# ETH-IO_v3_1.net
KiCad netlist of a schematic drawn in EAGLE
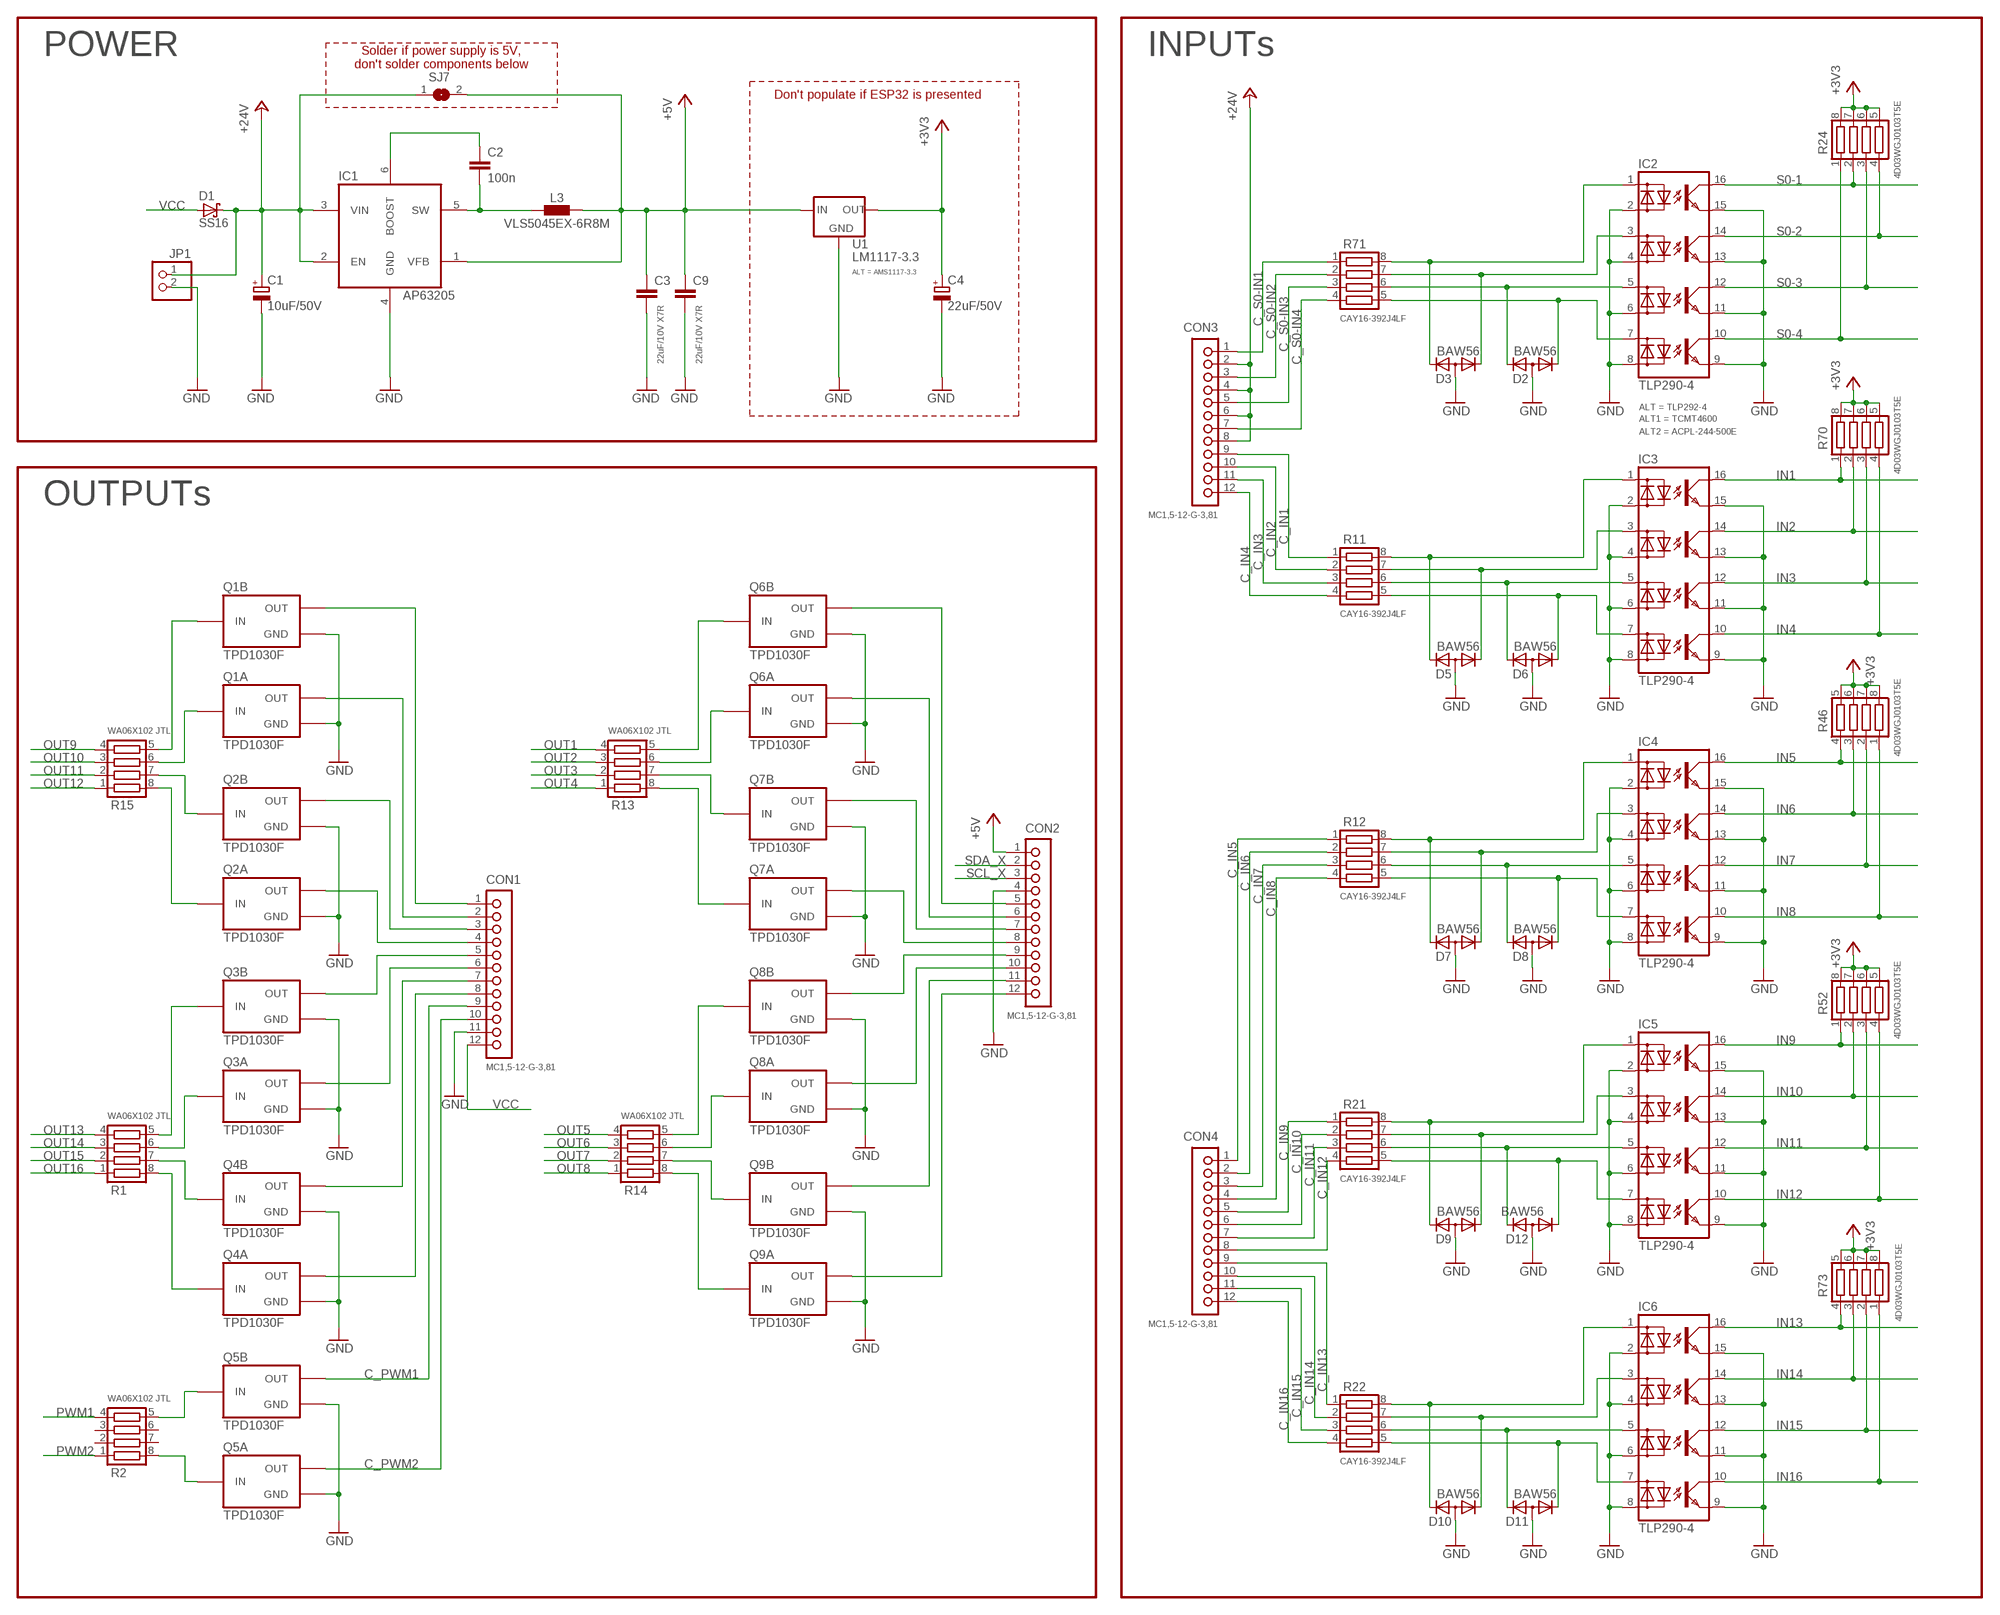
[diagram p0: schematic, sheet 1, part 1 of 2]
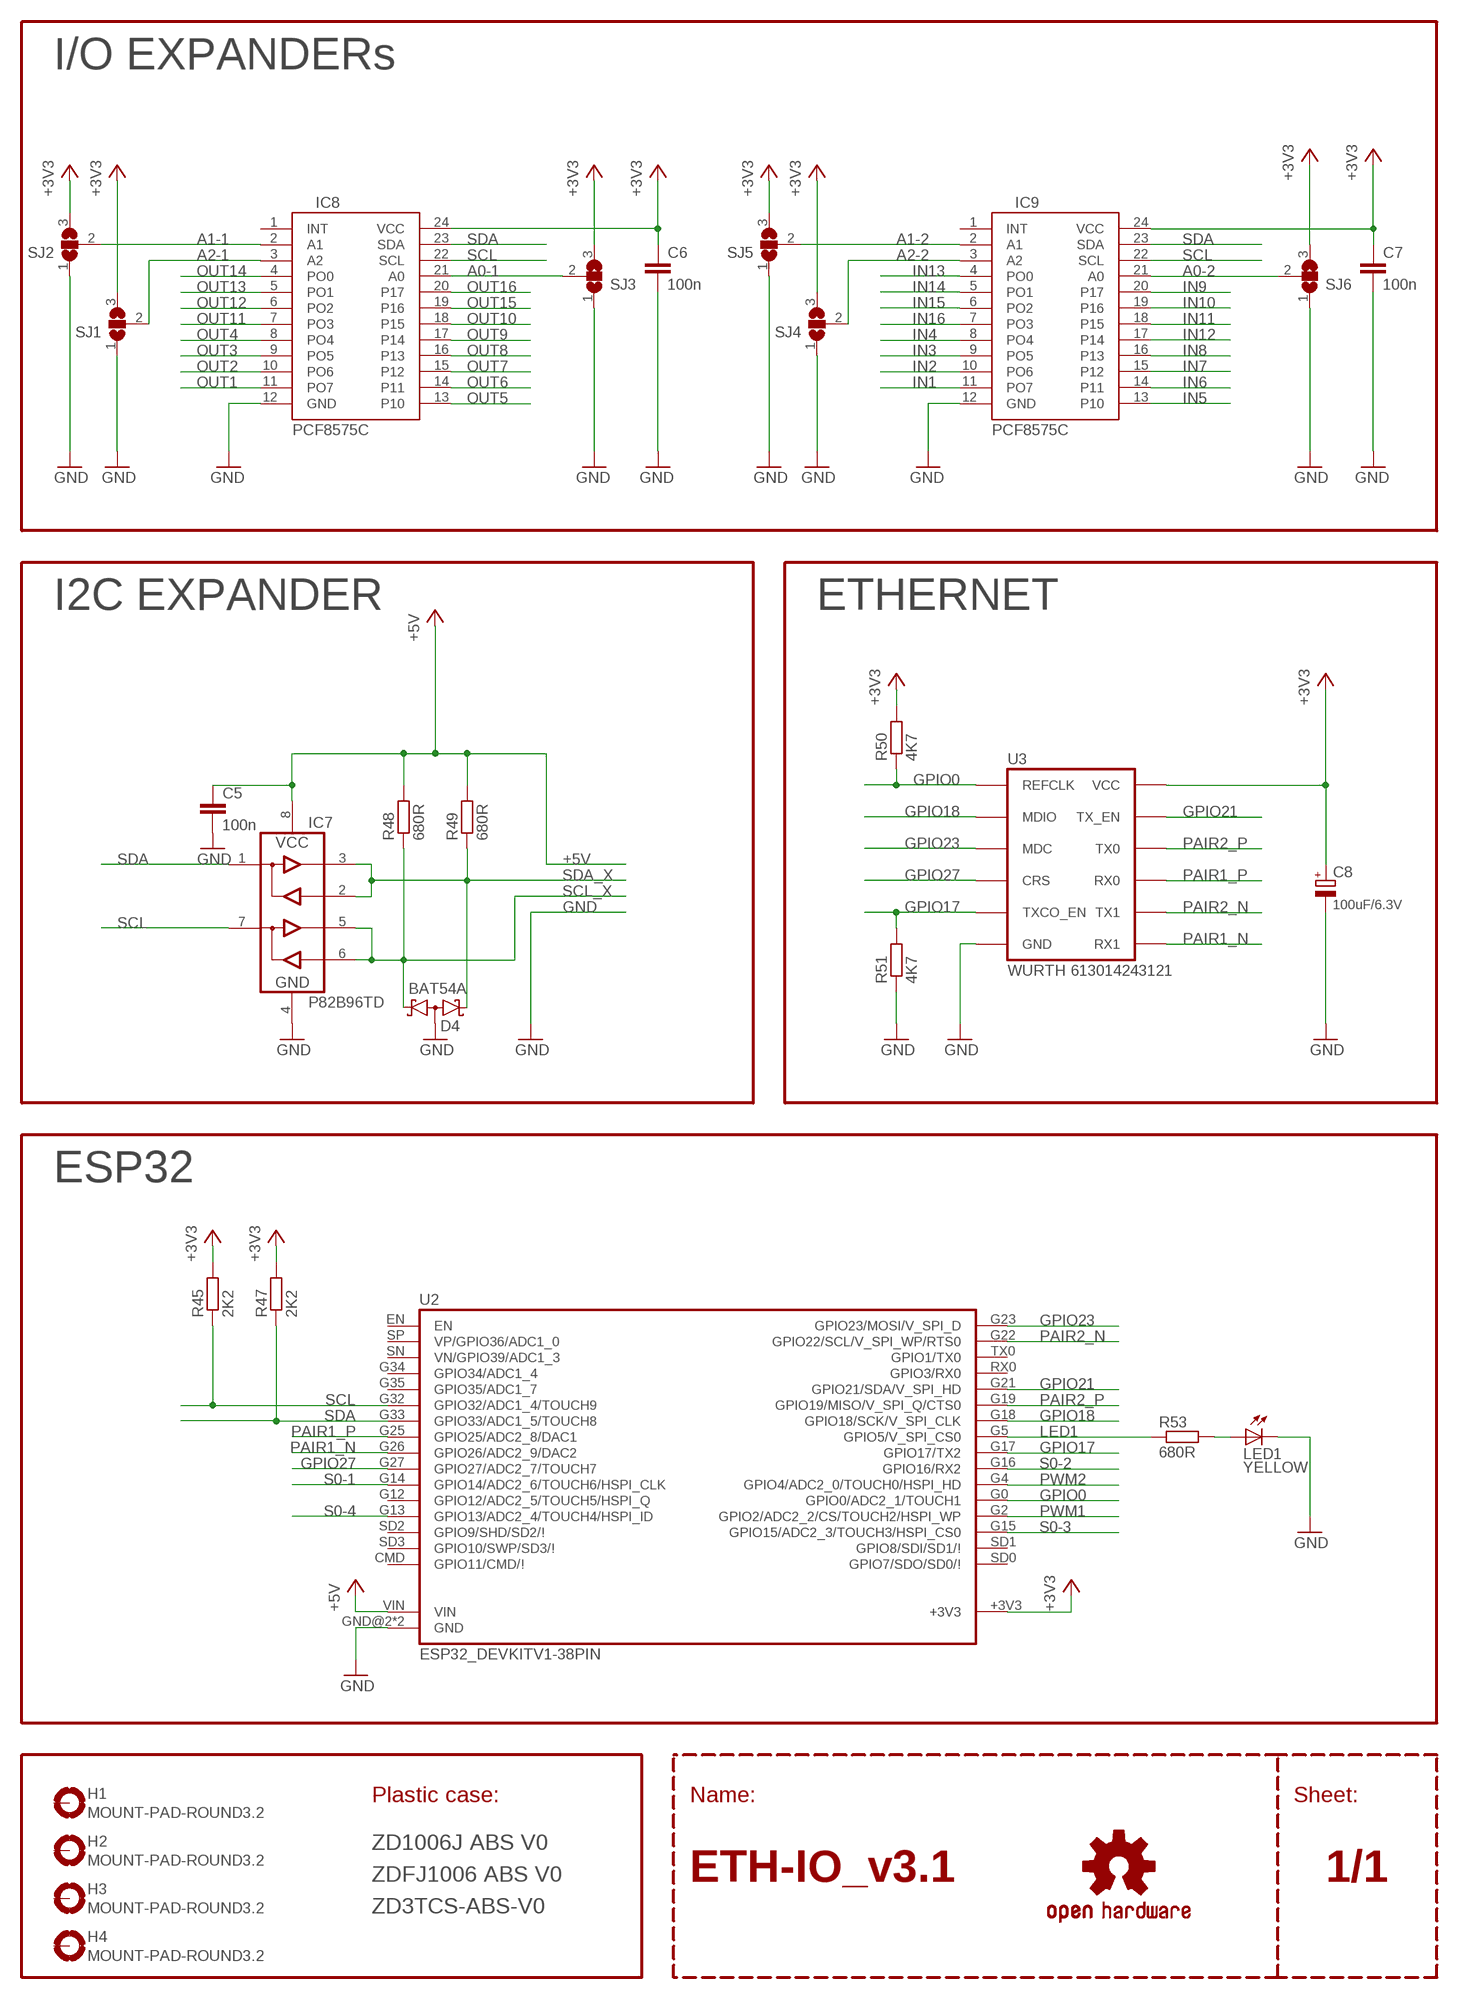
[diagram p1: schematic, sheet 1, part 2 of 2]

(export (version "E")
  (design (tool "Eeschema 10.0.6"))
  (components
    (comp (ref "C1")
      (value "10uF/50V")
      (footprint "eagle-import:PANASONIC_C")
      (libsource (lib "eagle-import") (part "CPOL-EUC"))
    )
    (comp (ref "C2")
      (value "100n")
      (footprint "eagle-import:C0805")
      (libsource (lib "eagle-import") (part "C-EUC0805"))
    )
    (comp (ref "C3")
      (value "22uF/10V X7R")
      (footprint "eagle-import:C1206")
      (libsource (lib "eagle-import") (part "C-EUC1206"))
    )
    (comp (ref "C4")
      (value "22uF/50V")
      (footprint "eagle-import:PANASONIC_C")
      (libsource (lib "eagle-import") (part "CPOL-EUC"))
    )
    (comp (ref "C5")
      (value "100n")
      (footprint "eagle-import:C0805")
      (libsource (lib "eagle-import") (part "C-EUC0805"))
    )
    (comp (ref "C6")
      (value "100n")
      (footprint "eagle-import:C0805")
      (libsource (lib "eagle-import") (part "C-EUC0805"))
    )
    (comp (ref "C7")
      (value "100n")
      (footprint "eagle-import:C0805")
      (libsource (lib "eagle-import") (part "C-EUC0805"))
    )
    (comp (ref "C8")
      (value "100uF/6.3V")
      (footprint "eagle-import:PANASONIC_C")
      (libsource (lib "eagle-import") (part "CPOL-EUC"))
    )
    (comp (ref "C9")
      (value "22uF/10V X7R")
      (footprint "eagle-import:C1206")
      (libsource (lib "eagle-import") (part "C-EUC1206"))
    )
    (comp (ref "CON1")
      (value "MC1,5-12-G-3,81")
      (footprint "eagle-import:MC1,5_12-G-3,81")
      (libsource (lib "eagle-import") (part "MC1,5-12-G-?3,81"))
    )
    (comp (ref "CON2")
      (value "MC1,5-12-G-3,81")
      (footprint "eagle-import:MC1,5_12-G-3,81")
      (libsource (lib "eagle-import") (part "MC1,5-12-G-?3,81"))
    )
    (comp (ref "CON3")
      (value "MC1,5-12-G-3,81")
      (footprint "eagle-import:MC1,5_12-G-3,81")
      (libsource (lib "eagle-import") (part "MC1,5-12-G-?3,81"))
    )
    (comp (ref "CON4")
      (value "MC1,5-12-G-3,81")
      (footprint "eagle-import:MC1,5_12-G-3,81")
      (libsource (lib "eagle-import") (part "MC1,5-12-G-?3,81"))
    )
    (comp (ref "D1")
      (value "SS16")
      (footprint "eagle-import:DO214AC")
      (libsource (lib "eagle-import") (part "SS?16"))
    )
    (comp (ref "D2")
      (value "BAW56")
      (footprint "eagle-import:SOT23")
      (libsource (lib "eagle-import") (part "BAW56"))
    )
    (comp (ref "D3")
      (value "BAW56")
      (footprint "eagle-import:SOT23")
      (libsource (lib "eagle-import") (part "BAW56"))
    )
    (comp (ref "D4")
      (value "BAT54A")
      (footprint "eagle-import:SOT23")
      (libsource (lib "eagle-import") (part "BAT54A"))
    )
    (comp (ref "D5")
      (value "BAW56")
      (footprint "eagle-import:SOT23")
      (libsource (lib "eagle-import") (part "BAW56"))
    )
    (comp (ref "D6")
      (value "BAW56")
      (footprint "eagle-import:SOT23")
      (libsource (lib "eagle-import") (part "BAW56"))
    )
    (comp (ref "D7")
      (value "BAW56")
      (footprint "eagle-import:SOT23")
      (libsource (lib "eagle-import") (part "BAW56"))
    )
    (comp (ref "D8")
      (value "BAW56")
      (footprint "eagle-import:SOT23")
      (libsource (lib "eagle-import") (part "BAW56"))
    )
    (comp (ref "D9")
      (value "BAW56")
      (footprint "eagle-import:SOT23")
      (libsource (lib "eagle-import") (part "BAW56"))
    )
    (comp (ref "D10")
      (value "BAW56")
      (footprint "eagle-import:SOT23")
      (libsource (lib "eagle-import") (part "BAW56"))
    )
    (comp (ref "D11")
      (value "BAW56")
      (footprint "eagle-import:SOT23")
      (libsource (lib "eagle-import") (part "BAW56"))
    )
    (comp (ref "D12")
      (value "BAW56")
      (footprint "eagle-import:SOT23")
      (libsource (lib "eagle-import") (part "BAW56"))
    )
    (comp (ref "H1")
      (value "MOUNT-PAD-ROUND3.2")
      (footprint "eagle-import:3,2-PAD")
      (libsource (lib "eagle-import") (part "MOUNT-PAD-ROUND3.2"))
    )
    (comp (ref "H2")
      (value "MOUNT-PAD-ROUND3.2")
      (footprint "eagle-import:3,2-PAD")
      (libsource (lib "eagle-import") (part "MOUNT-PAD-ROUND3.2"))
    )
    (comp (ref "H3")
      (value "MOUNT-PAD-ROUND3.2")
      (footprint "eagle-import:3,2-PAD")
      (libsource (lib "eagle-import") (part "MOUNT-PAD-ROUND3.2"))
    )
    (comp (ref "H4")
      (value "MOUNT-PAD-ROUND3.2")
      (footprint "eagle-import:3,2-PAD")
      (libsource (lib "eagle-import") (part "MOUNT-PAD-ROUND3.2"))
    )
    (comp (ref "IC1")
      (value "AP63205")
      (footprint "eagle-import:SOT23-6")
      (libsource (lib "eagle-import") (part "AP63205"))
    )
    (comp (ref "IC2")
      (value "TLP290-4")
      (footprint "eagle-import:SO16")
      (fields
        (field (name "ALT") "TLP292-4")
        (field (name "ALT1") "TCMT4600")
        (field (name "ALT2") "ACPL-244-500E")
      )
      (libsource (lib "eagle-import") (part "TLP290-4"))
    )
    (comp (ref "IC3")
      (value "TLP290-4")
      (footprint "eagle-import:SO16")
      (libsource (lib "eagle-import") (part "TLP290-4"))
    )
    (comp (ref "IC4")
      (value "TLP290-4")
      (footprint "eagle-import:SO16")
      (libsource (lib "eagle-import") (part "TLP290-4"))
    )
    (comp (ref "IC5")
      (value "TLP290-4")
      (footprint "eagle-import:SO16")
      (libsource (lib "eagle-import") (part "TLP290-4"))
    )
    (comp (ref "IC6")
      (value "TLP290-4")
      (footprint "eagle-import:SO16")
      (libsource (lib "eagle-import") (part "TLP290-4"))
    )
    (comp (ref "IC7")
      (value "P82B96TD")
      (footprint "eagle-import:SO08")
      (libsource (lib "eagle-import") (part "P82B96?TD"))
    )
    (comp (ref "IC8")
      (value "PCF8575C")
      (footprint "eagle-import:SO-24DW")
      (libsource (lib "eagle-import") (part "PCF8575C"))
    )
    (comp (ref "IC9")
      (value "PCF8575C")
      (footprint "eagle-import:SO-24DW")
      (libsource (lib "eagle-import") (part "PCF8575C"))
    )
    (comp (ref "JP1")
      (value "PINHD-1X2")
      (footprint "eagle-import:1X02")
      (libsource (lib "eagle-import") (part "PINHD-1X2"))
    )
    (comp (ref "L3")
      (value "VLS5045EX-6R8M")
      (footprint "eagle-import:L5040-LONGER")
      (libsource (lib "eagle-import") (part "L?5045"))
    )
    (comp (ref "LED1")
      (value "YELLOW")
      (footprint "eagle-import:LED0805")
      (libsource (lib "eagle-import") (part "LED0805"))
    )
    (comp (ref "LOGO1")
      (value "OSHW-LOGOM-COPPER")
      (footprint "eagle-import:OSHW-LOGO-M_COPPER")
      (libsource (lib "eagle-import") (part "OSHW-LOGOM-COPPER"))
    )
    (comp (ref "Q1")
      (value "TPD1030F")
      (footprint "eagle-import:SO8")
      (libsource (lib "eagle-import") (part "BTS3410G"))
    )
    (comp (ref "Q2")
      (value "TPD1030F")
      (footprint "eagle-import:SO8")
      (libsource (lib "eagle-import") (part "BTS3410G"))
    )
    (comp (ref "Q3")
      (value "TPD1030F")
      (footprint "eagle-import:SO8")
      (libsource (lib "eagle-import") (part "BTS3410G"))
    )
    (comp (ref "Q4")
      (value "TPD1030F")
      (footprint "eagle-import:SO8")
      (libsource (lib "eagle-import") (part "BTS3410G"))
    )
    (comp (ref "Q5")
      (value "TPD1030F")
      (footprint "eagle-import:SO8")
      (libsource (lib "eagle-import") (part "BTS3410G"))
    )
    (comp (ref "Q6")
      (value "TPD1030F")
      (footprint "eagle-import:SO8")
      (libsource (lib "eagle-import") (part "BTS3410G"))
    )
    (comp (ref "Q7")
      (value "TPD1030F")
      (footprint "eagle-import:SO8")
      (libsource (lib "eagle-import") (part "BTS3410G"))
    )
    (comp (ref "Q8")
      (value "TPD1030F")
      (footprint "eagle-import:SO8")
      (libsource (lib "eagle-import") (part "BTS3410G"))
    )
    (comp (ref "Q9")
      (value "TPD1030F")
      (footprint "eagle-import:SO8")
      (libsource (lib "eagle-import") (part "BTS3410G"))
    )
    (comp (ref "R1")
      (value "WA06X102 JTL")
      (footprint "eagle-import:RESCAV80P320X160X60-8N")
      (libsource (lib "eagle-import") (part "RESISTOR-ARRAY-?1206"))
    )
    (comp (ref "R2")
      (value "WA06X102 JTL")
      (footprint "eagle-import:RESCAV80P320X160X60-8N")
      (libsource (lib "eagle-import") (part "RESISTOR-ARRAY-?1206"))
    )
    (comp (ref "R11")
      (value "CAY16-392J4LF")
      (footprint "eagle-import:RESCAV80P320X160X60-8N")
      (libsource (lib "eagle-import") (part "RESISTOR-ARRAY-?1206"))
    )
    (comp (ref "R12")
      (value "CAY16-392J4LF")
      (footprint "eagle-import:RESCAV80P320X160X60-8N")
      (libsource (lib "eagle-import") (part "RESISTOR-ARRAY-?1206"))
    )
    (comp (ref "R13")
      (value "WA06X102 JTL")
      (footprint "eagle-import:RESCAV80P320X160X60-8N")
      (libsource (lib "eagle-import") (part "RESISTOR-ARRAY-?1206"))
    )
    (comp (ref "R14")
      (value "WA06X102 JTL")
      (footprint "eagle-import:RESCAV80P320X160X60-8N")
      (libsource (lib "eagle-import") (part "RESISTOR-ARRAY-?1206"))
    )
    (comp (ref "R15")
      (value "WA06X102 JTL")
      (footprint "eagle-import:RESCAV80P320X160X60-8N")
      (libsource (lib "eagle-import") (part "RESISTOR-ARRAY-?1206"))
    )
    (comp (ref "R21")
      (value "CAY16-392J4LF")
      (footprint "eagle-import:RESCAV80P320X160X60-8N")
      (libsource (lib "eagle-import") (part "RESISTOR-ARRAY-?1206"))
    )
    (comp (ref "R22")
      (value "CAY16-392J4LF")
      (footprint "eagle-import:RESCAV80P320X160X60-8N")
      (libsource (lib "eagle-import") (part "RESISTOR-ARRAY-?1206"))
    )
    (comp (ref "R24")
      (value "4D03WGJ0103T5E")
      (footprint "eagle-import:RESCAV80P320X160X60-8N")
      (libsource (lib "eagle-import") (part "RESISTOR-ARRAY-?1206"))
    )
    (comp (ref "R45")
      (value "2K2")
      (footprint "eagle-import:R0805")
      (libsource (lib "eagle-import") (part "R-EU_R0805"))
    )
    (comp (ref "R46")
      (value "4D03WGJ0103T5E")
      (footprint "eagle-import:RESCAV80P320X160X60-8N")
      (libsource (lib "eagle-import") (part "RESISTOR-ARRAY-?1206"))
    )
    (comp (ref "R47")
      (value "2K2")
      (footprint "eagle-import:R0805")
      (libsource (lib "eagle-import") (part "R-EU_R0805"))
    )
    (comp (ref "R48")
      (value "680R")
      (footprint "eagle-import:R0805")
      (libsource (lib "eagle-import") (part "R-EU_R0805"))
    )
    (comp (ref "R49")
      (value "680R")
      (footprint "eagle-import:R0805")
      (libsource (lib "eagle-import") (part "R-EU_R0805"))
    )
    (comp (ref "R50")
      (value "4K7")
      (footprint "eagle-import:R0805")
      (libsource (lib "eagle-import") (part "R-EU_R0805"))
    )
    (comp (ref "R51")
      (value "4K7")
      (footprint "eagle-import:R0805")
      (libsource (lib "eagle-import") (part "R-EU_R0805"))
    )
    (comp (ref "R52")
      (value "4D03WGJ0103T5E")
      (footprint "eagle-import:RESCAV80P320X160X60-8N")
      (libsource (lib "eagle-import") (part "RESISTOR-ARRAY-?1206"))
    )
    (comp (ref "R53")
      (value "680R")
      (footprint "eagle-import:R0805")
      (libsource (lib "eagle-import") (part "R-EU_R0805"))
    )
    (comp (ref "R70")
      (value "4D03WGJ0103T5E")
      (footprint "eagle-import:RESCAV80P320X160X60-8N")
      (libsource (lib "eagle-import") (part "RESISTOR-ARRAY-?1206"))
    )
    (comp (ref "R71")
      (value "CAY16-392J4LF")
      (footprint "eagle-import:RESCAV80P320X160X60-8N")
      (libsource (lib "eagle-import") (part "RESISTOR-ARRAY-?1206"))
    )
    (comp (ref "R73")
      (value "4D03WGJ0103T5E")
      (footprint "eagle-import:RESCAV80P320X160X60-8N")
      (libsource (lib "eagle-import") (part "RESISTOR-ARRAY-?1206"))
    )
    (comp (ref "SJ1")
      (value "SJ2W")
      (footprint "eagle-import:SJ_2")
      (libsource (lib "eagle-import") (part "SJ2W"))
    )
    (comp (ref "SJ2")
      (value "SJ2W")
      (footprint "eagle-import:SJ_2")
      (libsource (lib "eagle-import") (part "SJ2W"))
    )
    (comp (ref "SJ3")
      (value "SJ2W")
      (footprint "eagle-import:SJ_2")
      (libsource (lib "eagle-import") (part "SJ2W"))
    )
    (comp (ref "SJ4")
      (value "SJ2W")
      (footprint "eagle-import:SJ_2")
      (libsource (lib "eagle-import") (part "SJ2W"))
    )
    (comp (ref "SJ5")
      (value "SJ2W")
      (footprint "eagle-import:SJ_2")
      (libsource (lib "eagle-import") (part "SJ2W"))
    )
    (comp (ref "SJ6")
      (value "SJ2W")
      (footprint "eagle-import:SJ_2")
      (libsource (lib "eagle-import") (part "SJ2W"))
    )
    (comp (ref "SJ7") (value "SJ") (footprint "eagle-import:SJ") (libsource (lib "eagle-import") (part "SJ")))
    (comp (ref "U1")
      (value "LM1117-3.3")
      (footprint "eagle-import:SOT223")
      (fields (field (name "ALT") "AMS1117-3.3"))
      (libsource (lib "eagle-import") (part "LM1117-3.3"))
    )
    (comp (ref "U2")
      (value "ESP32_DEVKITV1-38PIN")
      (footprint "eagle-import:ESP32_DEVKITV1_38PIN")
      (libsource (lib "eagle-import") (part "ESP32_DEVKITV1-38PIN"))
    )
    (comp (ref "U3")
      (value "WURTH 613014243121")
      (footprint "eagle-import:LAN8720_ETH_BOARD")
      (libsource (lib "eagle-import") (part "LAN8720_ETH_BOARD"))
    )
  )
  (nets
    (net (code "1") (name "+3V3") (class "Default")
      (node (ref "C4") (pin "+") (pinfunction "+_+") (pintype "passive"))
      (node (ref "C6") (pin "1") (pinfunction "1_1") (pintype "passive"))
      (node (ref "C7") (pin "1") (pinfunction "1_1") (pintype "passive"))
      (node (ref "C8") (pin "+") (pinfunction "+_+") (pintype "passive"))
      (node (ref "IC8") (pin "24") (pinfunction "VCC_24") (pintype "bidirectional"))
      (node (ref "IC9") (pin "24") (pinfunction "VCC_24") (pintype "bidirectional"))
      (node (ref "R24") (pin "5") (pinfunction "4_5") (pintype "passive"))
      (node (ref "R24") (pin "6") (pinfunction "3_6") (pintype "passive"))
      (node (ref "R24") (pin "7") (pinfunction "2_7") (pintype "passive"))
      (node (ref "R24") (pin "8") (pinfunction "1_8") (pintype "passive"))
      (node (ref "R45") (pin "2") (pinfunction "2_2") (pintype "passive"))
      (node (ref "R46") (pin "5") (pinfunction "4_5") (pintype "passive"))
      (node (ref "R46") (pin "6") (pinfunction "3_6") (pintype "passive"))
      (node (ref "R46") (pin "7") (pinfunction "2_7") (pintype "passive"))
      (node (ref "R46") (pin "8") (pinfunction "1_8") (pintype "passive"))
      (node (ref "R47") (pin "2") (pinfunction "2_2") (pintype "passive"))
      (node (ref "R50") (pin "2") (pinfunction "2_2") (pintype "passive"))
      (node (ref "R52") (pin "5") (pinfunction "4_5") (pintype "passive"))
      (node (ref "R52") (pin "6") (pinfunction "3_6") (pintype "passive"))
      (node (ref "R52") (pin "7") (pinfunction "2_7") (pintype "passive"))
      (node (ref "R52") (pin "8") (pinfunction "1_8") (pintype "passive"))
      (node (ref "R70") (pin "5") (pinfunction "4_5") (pintype "passive"))
      (node (ref "R70") (pin "6") (pinfunction "3_6") (pintype "passive"))
      (node (ref "R70") (pin "7") (pinfunction "2_7") (pintype "passive"))
      (node (ref "R70") (pin "8") (pinfunction "1_8") (pintype "passive"))
      (node (ref "R73") (pin "5") (pinfunction "4_5") (pintype "passive"))
      (node (ref "R73") (pin "6") (pinfunction "3_6") (pintype "passive"))
      (node (ref "R73") (pin "7") (pinfunction "2_7") (pintype "passive"))
      (node (ref "R73") (pin "8") (pinfunction "1_8") (pintype "passive"))
      (node (ref "SJ1") (pin "3") (pinfunction "3_3") (pintype "passive"))
      (node (ref "SJ2") (pin "3") (pinfunction "3_3") (pintype "passive"))
      (node (ref "SJ3") (pin "3") (pinfunction "3_3") (pintype "passive"))
      (node (ref "SJ4") (pin "3") (pinfunction "3_3") (pintype "passive"))
      (node (ref "SJ5") (pin "3") (pinfunction "3_3") (pintype "passive"))
      (node (ref "SJ6") (pin "3") (pinfunction "3_3") (pintype "passive"))
      (node (ref "U1") (pin "2") (pinfunction "OUT_2") (pintype "output"))
      (node (ref "U1") (pin "4") (pinfunction "OUT_4") (pintype "output"))
      (node (ref "U2") (pin "+3V3") (pinfunction "+3V3_+3V3") (pintype "power_in"))
      (node (ref "U3") (pin "VCC") (pinfunction "VCC_VCC") (pintype "power_in"))
      (node (ref "U3") (pin "VCC@1") (pinfunction "VCC_VCC@1") (pintype "power_in"))
    )
    (net (code "2") (name "+5V") (class "Default")
      (node (ref "C3") (pin "1") (pinfunction "1_1") (pintype "passive"))
      (node (ref "C5") (pin "1") (pinfunction "1_1") (pintype "passive"))
      (node (ref "C9") (pin "1") (pinfunction "1_1") (pintype "passive"))
      (node (ref "CON2") (pin "1") (pinfunction "1_1") (pintype "passive"))
      (node (ref "IC1") (pin "1") (pinfunction "VFB_1") (pintype "input"))
      (node (ref "IC7") (pin "8") (pinfunction "VCC_8") (pintype "power_in"))
      (node (ref "L3") (pin "1") (pinfunction "1_1") (pintype "passive"))
      (node (ref "R48") (pin "2") (pinfunction "2_2") (pintype "passive"))
      (node (ref "R49") (pin "2") (pinfunction "2_2") (pintype "passive"))
      (node (ref "SJ7") (pin "2") (pinfunction "2_2") (pintype "passive"))
      (node (ref "U1") (pin "3") (pinfunction "IN_3") (pintype "input"))
      (node (ref "U2") (pin "VIN") (pinfunction "VIN_VIN") (pintype "power_in"))
    )
    (net (code "3") (name "+24V") (class "Default")
      (node (ref "C1") (pin "+") (pinfunction "+_+") (pintype "passive"))
      (node (ref "CON3") (pin "2") (pinfunction "2_2") (pintype "passive"))
      (node (ref "CON3") (pin "4") (pinfunction "4_4") (pintype "passive"))
      (node (ref "CON3") (pin "6") (pinfunction "6_6") (pintype "passive"))
      (node (ref "CON3") (pin "8") (pinfunction "8_8") (pintype "passive"))
      (node (ref "D1") (pin "C") (pinfunction "C_C") (pintype "passive"))
      (node (ref "IC1") (pin "2") (pinfunction "EN_2") (pintype "input"))
      (node (ref "IC1") (pin "3") (pinfunction "VIN_3") (pintype "power_in"))
      (node (ref "JP1") (pin "1") (pinfunction "1_1") (pintype "passive"))
      (node (ref "SJ7") (pin "1") (pinfunction "1_1") (pintype "passive"))
    )
    (net (code "4") (name "/A0-1") (class "Default")
      (node (ref "IC8") (pin "21") (pinfunction "A0_21") (pintype "bidirectional"))
      (node (ref "SJ3") (pin "2") (pinfunction "2_2") (pintype "passive"))
    )
    (net (code "5") (name "/A0-2") (class "Default")
      (node (ref "IC9") (pin "21") (pinfunction "A0_21") (pintype "bidirectional"))
      (node (ref "SJ6") (pin "2") (pinfunction "2_2") (pintype "passive"))
    )
    (net (code "6") (name "/A1-1") (class "Default")
      (node (ref "IC8") (pin "2") (pinfunction "A1_2") (pintype "bidirectional"))
      (node (ref "SJ2") (pin "2") (pinfunction "2_2") (pintype "passive"))
    )
    (net (code "7") (name "/A1-2") (class "Default")
      (node (ref "IC9") (pin "2") (pinfunction "A1_2") (pintype "bidirectional"))
      (node (ref "SJ5") (pin "2") (pinfunction "2_2") (pintype "passive"))
    )
    (net (code "8") (name "/A2-1") (class "Default")
      (node (ref "IC8") (pin "3") (pinfunction "A2_3") (pintype "bidirectional"))
      (node (ref "SJ1") (pin "2") (pinfunction "2_2") (pintype "passive"))
    )
    (net (code "9") (name "/A2-2") (class "Default")
      (node (ref "IC9") (pin "3") (pinfunction "A2_3") (pintype "bidirectional"))
      (node (ref "SJ4") (pin "2") (pinfunction "2_2") (pintype "passive"))
    )
    (net (code "10") (name "/C_IN1") (class "Default")
      (node (ref "CON3") (pin "9") (pinfunction "9_9") (pintype "passive"))
      (node (ref "R11") (pin "1") (pinfunction "1_1") (pintype "passive"))
    )
    (net (code "11") (name "/C_IN2") (class "Default")
      (node (ref "CON3") (pin "10") (pinfunction "10_10") (pintype "passive"))
      (node (ref "R11") (pin "2") (pinfunction "2_2") (pintype "passive"))
    )
    (net (code "12") (name "/C_IN3") (class "Default")
      (node (ref "CON3") (pin "11") (pinfunction "11_11") (pintype "passive"))
      (node (ref "R11") (pin "3") (pinfunction "3_3") (pintype "passive"))
    )
    (net (code "13") (name "/C_IN4") (class "Default")
      (node (ref "CON3") (pin "12") (pinfunction "12_12") (pintype "passive"))
      (node (ref "R11") (pin "4") (pinfunction "4_4") (pintype "passive"))
    )
    (net (code "14") (name "/C_IN5") (class "Default")
      (node (ref "CON4") (pin "1") (pinfunction "1_1") (pintype "passive"))
      (node (ref "R12") (pin "1") (pinfunction "1_1") (pintype "passive"))
    )
    (net (code "15") (name "/C_IN6") (class "Default")
      (node (ref "CON4") (pin "2") (pinfunction "2_2") (pintype "passive"))
      (node (ref "R12") (pin "2") (pinfunction "2_2") (pintype "passive"))
    )
    (net (code "16") (name "/C_IN7") (class "Default")
      (node (ref "CON4") (pin "3") (pinfunction "3_3") (pintype "passive"))
      (node (ref "R12") (pin "3") (pinfunction "3_3") (pintype "passive"))
    )
    (net (code "17") (name "/C_IN8") (class "Default")
      (node (ref "CON4") (pin "4") (pinfunction "4_4") (pintype "passive"))
      (node (ref "R12") (pin "4") (pinfunction "4_4") (pintype "passive"))
    )
    (net (code "18") (name "/C_IN9") (class "Default")
      (node (ref "CON4") (pin "5") (pinfunction "5_5") (pintype "passive"))
      (node (ref "R21") (pin "1") (pinfunction "1_1") (pintype "passive"))
    )
    (net (code "19") (name "/C_IN10") (class "Default")
      (node (ref "CON4") (pin "6") (pinfunction "6_6") (pintype "passive"))
      (node (ref "R21") (pin "2") (pinfunction "2_2") (pintype "passive"))
    )
    (net (code "20") (name "/C_IN11") (class "Default")
      (node (ref "CON4") (pin "7") (pinfunction "7_7") (pintype "passive"))
      (node (ref "R21") (pin "3") (pinfunction "3_3") (pintype "passive"))
    )
    (net (code "21") (name "/C_IN12") (class "Default")
      (node (ref "CON4") (pin "8") (pinfunction "8_8") (pintype "passive"))
      (node (ref "R21") (pin "4") (pinfunction "4_4") (pintype "passive"))
    )
    (net (code "22") (name "/C_IN13") (class "Default")
      (node (ref "CON4") (pin "9") (pinfunction "9_9") (pintype "passive"))
      (node (ref "R22") (pin "1") (pinfunction "1_1") (pintype "passive"))
    )
    (net (code "23") (name "/C_IN14") (class "Default")
      (node (ref "CON4") (pin "10") (pinfunction "10_10") (pintype "passive"))
      (node (ref "R22") (pin "2") (pinfunction "2_2") (pintype "passive"))
    )
    (net (code "24") (name "/C_IN15") (class "Default")
      (node (ref "CON4") (pin "11") (pinfunction "11_11") (pintype "passive"))
      (node (ref "R22") (pin "3") (pinfunction "3_3") (pintype "passive"))
    )
    (net (code "25") (name "/C_IN16") (class "Default")
      (node (ref "CON4") (pin "12") (pinfunction "12_12") (pintype "passive"))
      (node (ref "R22") (pin "4") (pinfunction "4_4") (pintype "passive"))
    )
    (net (code "26") (name "/C_PWM1") (class "Default")
      (node (ref "CON1") (pin "9") (pinfunction "9_9") (pintype "passive"))
      (node (ref "Q5") (pin "5") (pinfunction "OUT_5") (pintype "output"))
      (node (ref "Q5") (pin "6") (pinfunction "OUT_6") (pintype "output"))
    )
    (net (code "27") (name "/C_PWM2") (class "Default")
      (node (ref "CON1") (pin "10") (pinfunction "10_10") (pintype "passive"))
      (node (ref "Q5") (pin "7") (pinfunction "OUT_7") (pintype "output"))
      (node (ref "Q5") (pin "8") (pinfunction "OUT_8") (pintype "output"))
    )
    (net (code "28") (name "/C_S0-IN1") (class "Default")
      (node (ref "CON3") (pin "1") (pinfunction "1_1") (pintype "passive"))
      (node (ref "R71") (pin "1") (pinfunction "1_1") (pintype "passive"))
    )
    (net (code "29") (name "/C_S0-IN2") (class "Default")
      (node (ref "CON3") (pin "3") (pinfunction "3_3") (pintype "passive"))
      (node (ref "R71") (pin "2") (pinfunction "2_2") (pintype "passive"))
    )
    (net (code "30") (name "/C_S0-IN3") (class "Default")
      (node (ref "CON3") (pin "5") (pinfunction "5_5") (pintype "passive"))
      (node (ref "R71") (pin "3") (pinfunction "3_3") (pintype "passive"))
    )
    (net (code "31") (name "/C_S0-IN4") (class "Default")
      (node (ref "CON3") (pin "7") (pinfunction "7_7") (pintype "passive"))
      (node (ref "R71") (pin "4") (pinfunction "4_4") (pintype "passive"))
    )
    (net (code "32") (name "/GPIO0") (class "Default")
      (node (ref "R50") (pin "1") (pinfunction "1_1") (pintype "passive"))
      (node (ref "U2") (pin "G0") (pinfunction "GPIO0/ADC2_1/TOUCH1_G0") (pintype "bidirectional"))
      (node (ref "U3") (pin "INT") (pinfunction "REFCLK_INT") (pintype "output"))
    )
    (net (code "33") (name "/GPIO17") (class "Default")
      (node (ref "R51") (pin "2") (pinfunction "2_2") (pintype "passive"))
      (node (ref "U2") (pin "G17") (pinfunction "GPIO17/TX2_G17") (pintype "output"))
      (node (ref "U3") (pin "TXCO_EN") (pinfunction "TXCO_EN_TXCO_EN") (pintype "input"))
    )
    (net (code "34") (name "/GPIO18") (class "Default")
      (node (ref "U2") (pin "G18") (pinfunction "GPIO18/SCK/V_SPI_CLK_G18") (pintype "bidirectional"))
      (node (ref "U3") (pin "MDIO") (pinfunction "MDIO_MDIO") (pintype "bidirectional"))
    )
    (net (code "35") (name "/GPIO21") (class "Default")
      (node (ref "U2") (pin "G21") (pinfunction "GPIO21/SDA/V_SPI_HD_G21") (pintype "bidirectional"))
      (node (ref "U3") (pin "TX_EN") (pinfunction "TX_EN_TX_EN") (pintype "input"))
    )
    (net (code "36") (name "/GPIO23") (class "Default")
      (node (ref "U2") (pin "G23") (pinfunction "GPIO23/MOSI/V_SPI_D_G23") (pintype "bidirectional"))
      (node (ref "U3") (pin "MDC") (pinfunction "MDC_MDC") (pintype "bidirectional"))
    )
    (net (code "37") (name "/GPIO27") (class "Default")
      (node (ref "U2") (pin "G27") (pinfunction "GPIO27/ADC2_7/TOUCH7_G27") (pintype "bidirectional"))
      (node (ref "U3") (pin "CRS") (pinfunction "CRS_CRS") (pintype "bidirectional"))
    )
    (net (code "38") (name "/IN1") (class "Default")
      (node (ref "IC3") (pin "16") (pinfunction "COL1_16") (pintype "passive"))
      (node (ref "IC9") (pin "11") (pinfunction "PO7_11") (pintype "bidirectional"))
      (node (ref "R70") (pin "1") (pinfunction "1_1") (pintype "passive"))
    )
    (net (code "39") (name "/IN2") (class "Default")
      (node (ref "IC3") (pin "14") (pinfunction "COL2_14") (pintype "passive"))
      (node (ref "IC9") (pin "10") (pinfunction "PO6_10") (pintype "bidirectional"))
      (node (ref "R70") (pin "2") (pinfunction "2_2") (pintype "passive"))
    )
    (net (code "40") (name "/IN3") (class "Default")
      (node (ref "IC3") (pin "12") (pinfunction "COL3_12") (pintype "passive"))
      (node (ref "IC9") (pin "9") (pinfunction "PO5_9") (pintype "bidirectional"))
      (node (ref "R70") (pin "3") (pinfunction "3_3") (pintype "passive"))
    )
    (net (code "41") (name "/IN4") (class "Default")
      (node (ref "IC3") (pin "10") (pinfunction "COL4_10") (pintype "passive"))
      (node (ref "IC9") (pin "8") (pinfunction "PO4_8") (pintype "bidirectional"))
      (node (ref "R70") (pin "4") (pinfunction "4_4") (pintype "passive"))
    )
    (net (code "42") (name "/IN5") (class "Default")
      (node (ref "IC4") (pin "16") (pinfunction "COL1_16") (pintype "passive"))
      (node (ref "IC9") (pin "13") (pinfunction "P10_13") (pintype "bidirectional"))
      (node (ref "R46") (pin "4") (pinfunction "4_4") (pintype "passive"))
    )
    (net (code "43") (name "/IN6") (class "Default")
      (node (ref "IC4") (pin "14") (pinfunction "COL2_14") (pintype "passive"))
      (node (ref "IC9") (pin "14") (pinfunction "P11_14") (pintype "bidirectional"))
      (node (ref "R46") (pin "3") (pinfunction "3_3") (pintype "passive"))
    )
    (net (code "44") (name "/IN7") (class "Default")
      (node (ref "IC4") (pin "12") (pinfunction "COL3_12") (pintype "passive"))
      (node (ref "IC9") (pin "15") (pinfunction "P12_15") (pintype "bidirectional"))
      (node (ref "R46") (pin "2") (pinfunction "2_2") (pintype "passive"))
    )
    (net (code "45") (name "/IN8") (class "Default")
      (node (ref "IC4") (pin "10") (pinfunction "COL4_10") (pintype "passive"))
      (node (ref "IC9") (pin "16") (pinfunction "P13_16") (pintype "bidirectional"))
      (node (ref "R46") (pin "1") (pinfunction "1_1") (pintype "passive"))
    )
    (net (code "46") (name "/IN9") (class "Default")
      (node (ref "IC5") (pin "16") (pinfunction "COL1_16") (pintype "passive"))
      (node (ref "IC9") (pin "20") (pinfunction "P17_20") (pintype "bidirectional"))
      (node (ref "R52") (pin "1") (pinfunction "1_1") (pintype "passive"))
    )
    (net (code "47") (name "/IN10") (class "Default")
      (node (ref "IC5") (pin "14") (pinfunction "COL2_14") (pintype "passive"))
      (node (ref "IC9") (pin "19") (pinfunction "P16_19") (pintype "bidirectional"))
      (node (ref "R52") (pin "2") (pinfunction "2_2") (pintype "passive"))
    )
    (net (code "48") (name "/IN11") (class "Default")
      (node (ref "IC5") (pin "12") (pinfunction "COL3_12") (pintype "passive"))
      (node (ref "IC9") (pin "18") (pinfunction "P15_18") (pintype "bidirectional"))
      (node (ref "R52") (pin "3") (pinfunction "3_3") (pintype "passive"))
    )
    (net (code "49") (name "/IN12") (class "Default")
      (node (ref "IC5") (pin "10") (pinfunction "COL4_10") (pintype "passive"))
      (node (ref "IC9") (pin "17") (pinfunction "P14_17") (pintype "bidirectional"))
      (node (ref "R52") (pin "4") (pinfunction "4_4") (pintype "passive"))
    )
    (net (code "50") (name "/IN13") (class "Default")
      (node (ref "IC6") (pin "16") (pinfunction "COL1_16") (pintype "passive"))
      (node (ref "IC9") (pin "4") (pinfunction "PO0_4") (pintype "bidirectional"))
      (node (ref "R73") (pin "4") (pinfunction "4_4") (pintype "passive"))
    )
    (net (code "51") (name "/IN14") (class "Default")
      (node (ref "IC6") (pin "14") (pinfunction "COL2_14") (pintype "passive"))
      (node (ref "IC9") (pin "5") (pinfunction "PO1_5") (pintype "bidirectional"))
      (node (ref "R73") (pin "3") (pinfunction "3_3") (pintype "passive"))
    )
    (net (code "52") (name "/IN15") (class "Default")
      (node (ref "IC6") (pin "12") (pinfunction "COL3_12") (pintype "passive"))
      (node (ref "IC9") (pin "6") (pinfunction "PO2_6") (pintype "bidirectional"))
      (node (ref "R73") (pin "2") (pinfunction "2_2") (pintype "passive"))
    )
    (net (code "53") (name "/IN16") (class "Default")
      (node (ref "IC6") (pin "10") (pinfunction "COL4_10") (pintype "passive"))
      (node (ref "IC9") (pin "7") (pinfunction "PO3_7") (pintype "bidirectional"))
      (node (ref "R73") (pin "1") (pinfunction "1_1") (pintype "passive"))
    )
    (net (code "54") (name "/LED1") (class "Default")
      (node (ref "R53") (pin "1") (pinfunction "1_1") (pintype "passive"))
      (node (ref "U2") (pin "G5") (pinfunction "GPIO5/V_SPI_CS0_G5") (pintype "bidirectional"))
    )
    (net (code "55") (name "/OUT1") (class "Default")
      (node (ref "IC8") (pin "11") (pinfunction "PO7_11") (pintype "bidirectional"))
      (node (ref "R13") (pin "4") (pinfunction "4_4") (pintype "passive"))
    )
    (net (code "56") (name "/OUT2") (class "Default")
      (node (ref "IC8") (pin "10") (pinfunction "PO6_10") (pintype "bidirectional"))
      (node (ref "R13") (pin "3") (pinfunction "3_3") (pintype "passive"))
    )
    (net (code "57") (name "/OUT3") (class "Default")
      (node (ref "IC8") (pin "9") (pinfunction "PO5_9") (pintype "bidirectional"))
      (node (ref "R13") (pin "2") (pinfunction "2_2") (pintype "passive"))
    )
    (net (code "58") (name "/OUT4") (class "Default")
      (node (ref "IC8") (pin "8") (pinfunction "PO4_8") (pintype "bidirectional"))
      (node (ref "R13") (pin "1") (pinfunction "1_1") (pintype "passive"))
    )
    (net (code "59") (name "/OUT5") (class "Default")
      (node (ref "IC8") (pin "13") (pinfunction "P10_13") (pintype "bidirectional"))
      (node (ref "R14") (pin "4") (pinfunction "4_4") (pintype "passive"))
    )
    (net (code "60") (name "/OUT6") (class "Default")
      (node (ref "IC8") (pin "14") (pinfunction "P11_14") (pintype "bidirectional"))
      (node (ref "R14") (pin "3") (pinfunction "3_3") (pintype "passive"))
    )
    (net (code "61") (name "/OUT7") (class "Default")
      (node (ref "IC8") (pin "15") (pinfunction "P12_15") (pintype "bidirectional"))
      (node (ref "R14") (pin "2") (pinfunction "2_2") (pintype "passive"))
    )
    (net (code "62") (name "/OUT8") (class "Default")
      (node (ref "IC8") (pin "16") (pinfunction "P13_16") (pintype "bidirectional"))
      (node (ref "R14") (pin "1") (pinfunction "1_1") (pintype "passive"))
    )
    (net (code "63") (name "/OUT9") (class "Default")
      (node (ref "IC8") (pin "17") (pinfunction "P14_17") (pintype "bidirectional"))
      (node (ref "R15") (pin "4") (pinfunction "4_4") (pintype "passive"))
    )
    (net (code "64") (name "/OUT10") (class "Default")
      (node (ref "IC8") (pin "18") (pinfunction "P15_18") (pintype "bidirectional"))
      (node (ref "R15") (pin "3") (pinfunction "3_3") (pintype "passive"))
    )
    (net (code "65") (name "/OUT11") (class "Default")
      (node (ref "IC8") (pin "7") (pinfunction "PO3_7") (pintype "bidirectional"))
      (node (ref "R15") (pin "2") (pinfunction "2_2") (pintype "passive"))
    )
    (net (code "66") (name "/OUT12") (class "Default")
      (node (ref "IC8") (pin "6") (pinfunction "PO2_6") (pintype "bidirectional"))
      (node (ref "R15") (pin "1") (pinfunction "1_1") (pintype "passive"))
    )
    (net (code "67") (name "/OUT13") (class "Default")
      (node (ref "IC8") (pin "5") (pinfunction "PO1_5") (pintype "bidirectional"))
      (node (ref "R1") (pin "4") (pinfunction "4_4") (pintype "passive"))
    )
    (net (code "68") (name "/OUT14") (class "Default")
      (node (ref "IC8") (pin "4") (pinfunction "PO0_4") (pintype "bidirectional"))
      (node (ref "R1") (pin "3") (pinfunction "3_3") (pintype "passive"))
    )
    (net (code "69") (name "/OUT15") (class "Default")
      (node (ref "IC8") (pin "19") (pinfunction "P16_19") (pintype "bidirectional"))
      (node (ref "R1") (pin "2") (pinfunction "2_2") (pintype "passive"))
    )
    (net (code "70") (name "/OUT16") (class "Default")
      (node (ref "IC8") (pin "20") (pinfunction "P17_20") (pintype "bidirectional"))
      (node (ref "R1") (pin "1") (pinfunction "1_1") (pintype "passive"))
    )
    (net (code "71") (name "/PAIR1_N") (class "Default")
      (node (ref "U2") (pin "G26") (pinfunction "GPIO26/ADC2_9/DAC2_G26") (pintype "bidirectional"))
      (node (ref "U3") (pin "RX1") (pinfunction "RX1_RX1") (pintype "input"))
    )
    (net (code "72") (name "/PAIR1_P") (class "Default")
      (node (ref "U2") (pin "G25") (pinfunction "GPIO25/ADC2_8/DAC1_G25") (pintype "bidirectional"))
      (node (ref "U3") (pin "RX0") (pinfunction "RX0_RX0") (pintype "input"))
    )
    (net (code "73") (name "/PAIR2_N") (class "Default")
      (node (ref "U2") (pin "G22") (pinfunction "GPIO22/SCL/V_SPI_WP/RTS0_G22") (pintype "bidirectional"))
      (node (ref "U3") (pin "TX1") (pinfunction "TX1_TX1") (pintype "output"))
    )
    (net (code "74") (name "/PAIR2_P") (class "Default")
      (node (ref "U2") (pin "G19") (pinfunction "GPIO19/MISO/V_SPI_Q/CTS0_G19") (pintype "bidirectional"))
      (node (ref "U3") (pin "TX0") (pinfunction "TX0_TX0") (pintype "output"))
    )
    (net (code "75") (name "/PWM1") (class "Default")
      (node (ref "R2") (pin "4") (pinfunction "4_4") (pintype "passive"))
      (node (ref "U2") (pin "G2") (pinfunction "GPIO2/ADC2_2/CS/TOUCH2/HSPI_WP_G2") (pintype "bidirectional"))
    )
    (net (code "76") (name "/PWM2") (class "Default")
      (node (ref "R2") (pin "1") (pinfunction "1_1") (pintype "passive"))
      (node (ref "U2") (pin "G4") (pinfunction "GPIO4/ADC2_0/TOUCH0/HSPI_HD_G4") (pintype "bidirectional"))
    )
    (net (code "77") (name "/S0-1") (class "Default")
      (node (ref "IC2") (pin "16") (pinfunction "COL1_16") (pintype "passive"))
      (node (ref "R24") (pin "2") (pinfunction "2_2") (pintype "passive"))
      (node (ref "U2") (pin "G14") (pinfunction "GPIO14/ADC2_6/TOUCH6/HSPI_CLK_G14") (pintype "bidirectional"))
    )
    (net (code "78") (name "/S0-2") (class "Default")
      (node (ref "IC2") (pin "14") (pinfunction "COL2_14") (pintype "passive"))
      (node (ref "R24") (pin "4") (pinfunction "4_4") (pintype "passive"))
      (node (ref "U2") (pin "G16") (pinfunction "GPIO16/RX2_G16") (pintype "input"))
    )
    (net (code "79") (name "/S0-3") (class "Default")
      (node (ref "IC2") (pin "12") (pinfunction "COL3_12") (pintype "passive"))
      (node (ref "R24") (pin "3") (pinfunction "3_3") (pintype "passive"))
      (node (ref "U2") (pin "G15") (pinfunction "GPIO15/ADC2_3/TOUCH3/HSPI_CS0_G15") (pintype "bidirectional"))
    )
    (net (code "80") (name "/S0-4") (class "Default")
      (node (ref "IC2") (pin "10") (pinfunction "COL4_10") (pintype "passive"))
      (node (ref "R24") (pin "1") (pinfunction "1_1") (pintype "passive"))
      (node (ref "U2") (pin "G13") (pinfunction "GPIO13/ADC2_4/TOUCH4/HSPI_ID_G13") (pintype "bidirectional"))
    )
    (net (code "81") (name "/SCL") (class "Default")
      (node (ref "IC7") (pin "7") (pinfunction "SY_7") (pintype "input"))
      (node (ref "IC8") (pin "22") (pinfunction "SCL_22") (pintype "bidirectional"))
      (node (ref "IC9") (pin "22") (pinfunction "SCL_22") (pintype "bidirectional"))
      (node (ref "R45") (pin "1") (pinfunction "1_1") (pintype "passive"))
      (node (ref "U2") (pin "G32") (pinfunction "GPIO32/ADC1_4/TOUCH9_G32") (pintype "bidirectional"))
    )
    (net (code "82") (name "/SCL_X") (class "Default")
      (node (ref "CON2") (pin "3") (pinfunction "3_3") (pintype "passive"))
      (node (ref "D4") (pin "1") (pinfunction "K1_1") (pintype "passive"))
      (node (ref "IC7") (pin "5") (pinfunction "TY_5") (pintype "open_collector"))
      (node (ref "IC7") (pin "6") (pinfunction "RY_6") (pintype "open_collector"))
      (node (ref "R48") (pin "1") (pinfunction "1_1") (pintype "passive"))
    )
    (net (code "83") (name "/SDA") (class "Default")
      (node (ref "IC7") (pin "1") (pinfunction "SX_1") (pintype "input"))
      (node (ref "IC8") (pin "23") (pinfunction "SDA_23") (pintype "bidirectional"))
      (node (ref "IC9") (pin "23") (pinfunction "SDA_23") (pintype "bidirectional"))
      (node (ref "R47") (pin "1") (pinfunction "1_1") (pintype "passive"))
      (node (ref "U2") (pin "G33") (pinfunction "GPIO33/ADC1_5/TOUCH8_G33") (pintype "bidirectional"))
    )
    (net (code "84") (name "/SDA_X") (class "Default")
      (node (ref "CON2") (pin "2") (pinfunction "2_2") (pintype "passive"))
      (node (ref "D4") (pin "2") (pinfunction "K2_2") (pintype "passive"))
      (node (ref "IC7") (pin "2") (pinfunction "RX_2") (pintype "open_collector"))
      (node (ref "IC7") (pin "3") (pinfunction "TX_3") (pintype "open_collector"))
      (node (ref "R49") (pin "1") (pinfunction "1_1") (pintype "passive"))
    )
    (net (code "85") (name "/VCC") (class "Default")
      (node (ref "CON1") (pin "12") (pinfunction "12_12") (pintype "passive"))
      (node (ref "D1") (pin "A") (pinfunction "A_A") (pintype "passive"))
    )
    (net (code "86") (name "GND") (class "Default")
      (node (ref "C1") (pin "-") (pinfunction "-_-") (pintype "passive"))
      (node (ref "C3") (pin "2") (pinfunction "2_2") (pintype "passive"))
      (node (ref "C4") (pin "-") (pinfunction "-_-") (pintype "passive"))
      (node (ref "C5") (pin "2") (pinfunction "2_2") (pintype "passive"))
      (node (ref "C6") (pin "2") (pinfunction "2_2") (pintype "passive"))
      (node (ref "C7") (pin "2") (pinfunction "2_2") (pintype "passive"))
      (node (ref "C8") (pin "-") (pinfunction "-_-") (pintype "passive"))
      (node (ref "C9") (pin "2") (pinfunction "2_2") (pintype "passive"))
      (node (ref "CON1") (pin "11") (pinfunction "11_11") (pintype "passive"))
      (node (ref "CON2") (pin "4") (pinfunction "4_4") (pintype "passive"))
      (node (ref "D10") (pin "3") (pinfunction "A_3") (pintype "passive"))
      (node (ref "D11") (pin "3") (pinfunction "A_3") (pintype "passive"))
      (node (ref "D12") (pin "3") (pinfunction "A_3") (pintype "passive"))
      (node (ref "D2") (pin "3") (pinfunction "A_3") (pintype "passive"))
      (node (ref "D3") (pin "3") (pinfunction "A_3") (pintype "passive"))
      (node (ref "D4") (pin "3") (pinfunction "AA_3") (pintype "passive"))
      (node (ref "D5") (pin "3") (pinfunction "A_3") (pintype "passive"))
      (node (ref "D6") (pin "3") (pinfunction "A_3") (pintype "passive"))
      (node (ref "D7") (pin "3") (pinfunction "A_3") (pintype "passive"))
      (node (ref "D8") (pin "3") (pinfunction "A_3") (pintype "passive"))
      (node (ref "D9") (pin "3") (pinfunction "A_3") (pintype "passive"))
      (node (ref "IC1") (pin "4") (pinfunction "GND_4") (pintype "power_in"))
      (node (ref "IC2") (pin "11") (pinfunction "EMIT3_11") (pintype "passive"))
      (node (ref "IC2") (pin "13") (pinfunction "EMIT2_13") (pintype "passive"))
      (node (ref "IC2") (pin "15") (pinfunction "EMIT1_15") (pintype "passive"))
      (node (ref "IC2") (pin "2") (pinfunction "C1_2") (pintype "passive"))
      (node (ref "IC2") (pin "4") (pinfunction "C2_4") (pintype "passive"))
      (node (ref "IC2") (pin "6") (pinfunction "C3_6") (pintype "passive"))
      (node (ref "IC2") (pin "8") (pinfunction "C4_8") (pintype "passive"))
      (node (ref "IC2") (pin "9") (pinfunction "EMIT4_9") (pintype "passive"))
      (node (ref "IC3") (pin "11") (pinfunction "EMIT3_11") (pintype "passive"))
      (node (ref "IC3") (pin "13") (pinfunction "EMIT2_13") (pintype "passive"))
      (node (ref "IC3") (pin "15") (pinfunction "EMIT1_15") (pintype "passive"))
      (node (ref "IC3") (pin "2") (pinfunction "C1_2") (pintype "passive"))
      (node (ref "IC3") (pin "4") (pinfunction "C2_4") (pintype "passive"))
      (node (ref "IC3") (pin "6") (pinfunction "C3_6") (pintype "passive"))
      (node (ref "IC3") (pin "8") (pinfunction "C4_8") (pintype "passive"))
      (node (ref "IC3") (pin "9") (pinfunction "EMIT4_9") (pintype "passive"))
      (node (ref "IC4") (pin "11") (pinfunction "EMIT3_11") (pintype "passive"))
      (node (ref "IC4") (pin "13") (pinfunction "EMIT2_13") (pintype "passive"))
      (node (ref "IC4") (pin "15") (pinfunction "EMIT1_15") (pintype "passive"))
      (node (ref "IC4") (pin "2") (pinfunction "C1_2") (pintype "passive"))
      (node (ref "IC4") (pin "4") (pinfunction "C2_4") (pintype "passive"))
      (node (ref "IC4") (pin "6") (pinfunction "C3_6") (pintype "passive"))
      (node (ref "IC4") (pin "8") (pinfunction "C4_8") (pintype "passive"))
      (node (ref "IC4") (pin "9") (pinfunction "EMIT4_9") (pintype "passive"))
      (node (ref "IC5") (pin "11") (pinfunction "EMIT3_11") (pintype "passive"))
      (node (ref "IC5") (pin "13") (pinfunction "EMIT2_13") (pintype "passive"))
      (node (ref "IC5") (pin "15") (pinfunction "EMIT1_15") (pintype "passive"))
      (node (ref "IC5") (pin "2") (pinfunction "C1_2") (pintype "passive"))
      (node (ref "IC5") (pin "4") (pinfunction "C2_4") (pintype "passive"))
      (node (ref "IC5") (pin "6") (pinfunction "C3_6") (pintype "passive"))
      (node (ref "IC5") (pin "8") (pinfunction "C4_8") (pintype "passive"))
      (node (ref "IC5") (pin "9") (pinfunction "EMIT4_9") (pintype "passive"))
      (node (ref "IC6") (pin "11") (pinfunction "EMIT3_11") (pintype "passive"))
      (node (ref "IC6") (pin "13") (pinfunction "EMIT2_13") (pintype "passive"))
      (node (ref "IC6") (pin "15") (pinfunction "EMIT1_15") (pintype "passive"))
      (node (ref "IC6") (pin "2") (pinfunction "C1_2") (pintype "passive"))
      (node (ref "IC6") (pin "4") (pinfunction "C2_4") (pintype "passive"))
      (node (ref "IC6") (pin "6") (pinfunction "C3_6") (pintype "passive"))
      (node (ref "IC6") (pin "8") (pinfunction "C4_8") (pintype "passive"))
      (node (ref "IC6") (pin "9") (pinfunction "EMIT4_9") (pintype "passive"))
      (node (ref "IC7") (pin "4") (pinfunction "GND_4") (pintype "power_in"))
      (node (ref "IC8") (pin "12") (pinfunction "GND_12") (pintype "bidirectional"))
      (node (ref "IC9") (pin "12") (pinfunction "GND_12") (pintype "bidirectional"))
      (node (ref "JP1") (pin "2") (pinfunction "2_2") (pintype "passive"))
      (node (ref "LED1") (pin "C") (pinfunction "C_C") (pintype "passive"))
      (node (ref "Q1") (pin "1") (pinfunction "GND_1") (pintype "power_in"))
      (node (ref "Q1") (pin "3") (pinfunction "GND_3") (pintype "power_in"))
      (node (ref "Q2") (pin "1") (pinfunction "GND_1") (pintype "power_in"))
      (node (ref "Q2") (pin "3") (pinfunction "GND_3") (pintype "power_in"))
      (node (ref "Q3") (pin "1") (pinfunction "GND_1") (pintype "power_in"))
      (node (ref "Q3") (pin "3") (pinfunction "GND_3") (pintype "power_in"))
      (node (ref "Q4") (pin "1") (pinfunction "GND_1") (pintype "power_in"))
      (node (ref "Q4") (pin "3") (pinfunction "GND_3") (pintype "power_in"))
      (node (ref "Q5") (pin "1") (pinfunction "GND_1") (pintype "power_in"))
      (node (ref "Q5") (pin "3") (pinfunction "GND_3") (pintype "power_in"))
      (node (ref "Q6") (pin "1") (pinfunction "GND_1") (pintype "power_in"))
      (node (ref "Q6") (pin "3") (pinfunction "GND_3") (pintype "power_in"))
      (node (ref "Q7") (pin "1") (pinfunction "GND_1") (pintype "power_in"))
      (node (ref "Q7") (pin "3") (pinfunction "GND_3") (pintype "power_in"))
      (node (ref "Q8") (pin "1") (pinfunction "GND_1") (pintype "power_in"))
      (node (ref "Q8") (pin "3") (pinfunction "GND_3") (pintype "power_in"))
      (node (ref "Q9") (pin "1") (pinfunction "GND_1") (pintype "power_in"))
      (node (ref "Q9") (pin "3") (pinfunction "GND_3") (pintype "power_in"))
      (node (ref "R51") (pin "1") (pinfunction "1_1") (pintype "passive"))
      (node (ref "SJ1") (pin "1") (pinfunction "1_1") (pintype "passive"))
      (node (ref "SJ2") (pin "1") (pinfunction "1_1") (pintype "passive"))
      (node (ref "SJ3") (pin "1") (pinfunction "1_1") (pintype "passive"))
      (node (ref "SJ4") (pin "1") (pinfunction "1_1") (pintype "passive"))
      (node (ref "SJ5") (pin "1") (pinfunction "1_1") (pintype "passive"))
      (node (ref "SJ6") (pin "1") (pinfunction "1_1") (pintype "passive"))
      (node (ref "U1") (pin "1") (pinfunction "GND_1") (pintype "input"))
      (node (ref "U2") (pin "GND@2") (pinfunction "GND_GND@2") (pintype "power_in"))
      (node (ref "U2") (pin "GND@3") (pinfunction "GND_GND@3") (pintype "power_in"))
      (node (ref "U3") (pin "GND") (pinfunction "GND_GND") (pintype "power_in"))
      (node (ref "U3") (pin "GND@1") (pinfunction "GND_GND@1") (pintype "power_in"))
    )
    (net (code "87") (name "Net-(CON1-Pad1)") (class "Default")
      (node (ref "CON1") (pin "1") (pinfunction "1_1") (pintype "passive"))
      (node (ref "Q1") (pin "5") (pinfunction "OUT_5") (pintype "output"))
      (node (ref "Q1") (pin "6") (pinfunction "OUT_6") (pintype "output"))
    )
    (net (code "88") (name "Net-(CON1-Pad2)") (class "Default")
      (node (ref "CON1") (pin "2") (pinfunction "2_2") (pintype "passive"))
      (node (ref "Q1") (pin "7") (pinfunction "OUT_7") (pintype "output"))
      (node (ref "Q1") (pin "8") (pinfunction "OUT_8") (pintype "output"))
    )
    (net (code "89") (name "Net-(CON1-Pad3)") (class "Default")
      (node (ref "CON1") (pin "3") (pinfunction "3_3") (pintype "passive"))
      (node (ref "Q2") (pin "5") (pinfunction "OUT_5") (pintype "output"))
      (node (ref "Q2") (pin "6") (pinfunction "OUT_6") (pintype "output"))
    )
    (net (code "90") (name "Net-(CON1-Pad4)") (class "Default")
      (node (ref "CON1") (pin "4") (pinfunction "4_4") (pintype "passive"))
      (node (ref "Q2") (pin "7") (pinfunction "OUT_7") (pintype "output"))
      (node (ref "Q2") (pin "8") (pinfunction "OUT_8") (pintype "output"))
    )
    (net (code "91") (name "Net-(CON1-Pad5)") (class "Default")
      (node (ref "CON1") (pin "5") (pinfunction "5_5") (pintype "passive"))
      (node (ref "Q3") (pin "5") (pinfunction "OUT_5") (pintype "output"))
      (node (ref "Q3") (pin "6") (pinfunction "OUT_6") (pintype "output"))
    )
    (net (code "92") (name "Net-(CON1-Pad6)") (class "Default")
      (node (ref "CON1") (pin "6") (pinfunction "6_6") (pintype "passive"))
      (node (ref "Q3") (pin "7") (pinfunction "OUT_7") (pintype "output"))
      (node (ref "Q3") (pin "8") (pinfunction "OUT_8") (pintype "output"))
    )
    (net (code "93") (name "Net-(CON1-Pad7)") (class "Default")
      (node (ref "CON1") (pin "7") (pinfunction "7_7") (pintype "passive"))
      (node (ref "Q4") (pin "5") (pinfunction "OUT_5") (pintype "output"))
      (node (ref "Q4") (pin "6") (pinfunction "OUT_6") (pintype "output"))
    )
    (net (code "94") (name "Net-(CON1-Pad8)") (class "Default")
      (node (ref "CON1") (pin "8") (pinfunction "8_8") (pintype "passive"))
      (node (ref "Q4") (pin "7") (pinfunction "OUT_7") (pintype "output"))
      (node (ref "Q4") (pin "8") (pinfunction "OUT_8") (pintype "output"))
    )
    (net (code "95") (name "Net-(CON2-Pad5)") (class "Default")
      (node (ref "CON2") (pin "5") (pinfunction "5_5") (pintype "passive"))
      (node (ref "Q6") (pin "5") (pinfunction "OUT_5") (pintype "output"))
      (node (ref "Q6") (pin "6") (pinfunction "OUT_6") (pintype "output"))
    )
    (net (code "96") (name "Net-(CON2-Pad6)") (class "Default")
      (node (ref "CON2") (pin "6") (pinfunction "6_6") (pintype "passive"))
      (node (ref "Q6") (pin "7") (pinfunction "OUT_7") (pintype "output"))
      (node (ref "Q6") (pin "8") (pinfunction "OUT_8") (pintype "output"))
    )
    (net (code "97") (name "Net-(CON2-Pad7)") (class "Default")
      (node (ref "CON2") (pin "7") (pinfunction "7_7") (pintype "passive"))
      (node (ref "Q7") (pin "5") (pinfunction "OUT_5") (pintype "output"))
      (node (ref "Q7") (pin "6") (pinfunction "OUT_6") (pintype "output"))
    )
    (net (code "98") (name "Net-(CON2-Pad8)") (class "Default")
      (node (ref "CON2") (pin "8") (pinfunction "8_8") (pintype "passive"))
      (node (ref "Q7") (pin "7") (pinfunction "OUT_7") (pintype "output"))
      (node (ref "Q7") (pin "8") (pinfunction "OUT_8") (pintype "output"))
    )
    (net (code "99") (name "Net-(CON2-Pad9)") (class "Default")
      (node (ref "CON2") (pin "9") (pinfunction "9_9") (pintype "passive"))
      (node (ref "Q8") (pin "5") (pinfunction "OUT_5") (pintype "output"))
      (node (ref "Q8") (pin "6") (pinfunction "OUT_6") (pintype "output"))
    )
    (net (code "100") (name "Net-(CON2-Pad10)") (class "Default")
      (node (ref "CON2") (pin "10") (pinfunction "10_10") (pintype "passive"))
      (node (ref "Q8") (pin "7") (pinfunction "OUT_7") (pintype "output"))
      (node (ref "Q8") (pin "8") (pinfunction "OUT_8") (pintype "output"))
    )
    (net (code "101") (name "Net-(CON2-Pad11)") (class "Default")
      (node (ref "CON2") (pin "11") (pinfunction "11_11") (pintype "passive"))
      (node (ref "Q9") (pin "5") (pinfunction "OUT_5") (pintype "output"))
      (node (ref "Q9") (pin "6") (pinfunction "OUT_6") (pintype "output"))
    )
    (net (code "102") (name "Net-(CON2-Pad12)") (class "Default")
      (node (ref "CON2") (pin "12") (pinfunction "12_12") (pintype "passive"))
      (node (ref "Q9") (pin "7") (pinfunction "OUT_7") (pintype "output"))
      (node (ref "Q9") (pin "8") (pinfunction "OUT_8") (pintype "output"))
    )
    (net (code "103") (name "Net-(D2-K1)") (class "Default")
      (node (ref "D2") (pin "1") (pinfunction "K1_1") (pintype "passive"))
      (node (ref "IC2") (pin "7") (pinfunction "A4_7") (pintype "passive"))
      (node (ref "R71") (pin "5") (pinfunction "4_5") (pintype "passive"))
    )
    (net (code "104") (name "Net-(D2-K2)") (class "Default")
      (node (ref "D2") (pin "2") (pinfunction "K2_2") (pintype "passive"))
      (node (ref "IC2") (pin "5") (pinfunction "A3_5") (pintype "passive"))
      (node (ref "R71") (pin "6") (pinfunction "3_6") (pintype "passive"))
    )
    (net (code "105") (name "Net-(D3-K1)") (class "Default")
      (node (ref "D3") (pin "1") (pinfunction "K1_1") (pintype "passive"))
      (node (ref "IC2") (pin "3") (pinfunction "A2_3") (pintype "passive"))
      (node (ref "R71") (pin "7") (pinfunction "2_7") (pintype "passive"))
    )
    (net (code "106") (name "Net-(D3-K2)") (class "Default")
      (node (ref "D3") (pin "2") (pinfunction "K2_2") (pintype "passive"))
      (node (ref "IC2") (pin "1") (pinfunction "A1_1") (pintype "passive"))
      (node (ref "R71") (pin "8") (pinfunction "1_8") (pintype "passive"))
    )
    (net (code "107") (name "Net-(D5-K1)") (class "Default")
      (node (ref "D5") (pin "1") (pinfunction "K1_1") (pintype "passive"))
      (node (ref "IC3") (pin "3") (pinfunction "A2_3") (pintype "passive"))
      (node (ref "R11") (pin "7") (pinfunction "2_7") (pintype "passive"))
    )
    (net (code "108") (name "Net-(D5-K2)") (class "Default")
      (node (ref "D5") (pin "2") (pinfunction "K2_2") (pintype "passive"))
      (node (ref "IC3") (pin "1") (pinfunction "A1_1") (pintype "passive"))
      (node (ref "R11") (pin "8") (pinfunction "1_8") (pintype "passive"))
    )
    (net (code "109") (name "Net-(D6-K1)") (class "Default")
      (node (ref "D6") (pin "1") (pinfunction "K1_1") (pintype "passive"))
      (node (ref "IC3") (pin "7") (pinfunction "A4_7") (pintype "passive"))
      (node (ref "R11") (pin "5") (pinfunction "4_5") (pintype "passive"))
    )
    (net (code "110") (name "Net-(D6-K2)") (class "Default")
      (node (ref "D6") (pin "2") (pinfunction "K2_2") (pintype "passive"))
      (node (ref "IC3") (pin "5") (pinfunction "A3_5") (pintype "passive"))
      (node (ref "R11") (pin "6") (pinfunction "3_6") (pintype "passive"))
    )
    (net (code "111") (name "Net-(D7-K1)") (class "Default")
      (node (ref "D7") (pin "1") (pinfunction "K1_1") (pintype "passive"))
      (node (ref "IC4") (pin "3") (pinfunction "A2_3") (pintype "passive"))
      (node (ref "R12") (pin "7") (pinfunction "2_7") (pintype "passive"))
    )
    (net (code "112") (name "Net-(D7-K2)") (class "Default")
      (node (ref "D7") (pin "2") (pinfunction "K2_2") (pintype "passive"))
      (node (ref "IC4") (pin "1") (pinfunction "A1_1") (pintype "passive"))
      (node (ref "R12") (pin "8") (pinfunction "1_8") (pintype "passive"))
    )
    (net (code "113") (name "Net-(D8-K1)") (class "Default")
      (node (ref "D8") (pin "1") (pinfunction "K1_1") (pintype "passive"))
      (node (ref "IC4") (pin "7") (pinfunction "A4_7") (pintype "passive"))
      (node (ref "R12") (pin "5") (pinfunction "4_5") (pintype "passive"))
    )
    (net (code "114") (name "Net-(D8-K2)") (class "Default")
      (node (ref "D8") (pin "2") (pinfunction "K2_2") (pintype "passive"))
      (node (ref "IC4") (pin "5") (pinfunction "A3_5") (pintype "passive"))
      (node (ref "R12") (pin "6") (pinfunction "3_6") (pintype "passive"))
    )
    (net (code "115") (name "Net-(D9-K1)") (class "Default")
      (node (ref "D9") (pin "1") (pinfunction "K1_1") (pintype "passive"))
      (node (ref "IC5") (pin "3") (pinfunction "A2_3") (pintype "passive"))
      (node (ref "R21") (pin "7") (pinfunction "2_7") (pintype "passive"))
    )
    (net (code "116") (name "Net-(D9-K2)") (class "Default")
      (node (ref "D9") (pin "2") (pinfunction "K2_2") (pintype "passive"))
      (node (ref "IC5") (pin "1") (pinfunction "A1_1") (pintype "passive"))
      (node (ref "R21") (pin "8") (pinfunction "1_8") (pintype "passive"))
    )
    (net (code "117") (name "Net-(D10-K1)") (class "Default")
      (node (ref "D10") (pin "1") (pinfunction "K1_1") (pintype "passive"))
      (node (ref "IC6") (pin "3") (pinfunction "A2_3") (pintype "passive"))
      (node (ref "R22") (pin "7") (pinfunction "2_7") (pintype "passive"))
    )
    (net (code "118") (name "Net-(D10-K2)") (class "Default")
      (node (ref "D10") (pin "2") (pinfunction "K2_2") (pintype "passive"))
      (node (ref "IC6") (pin "1") (pinfunction "A1_1") (pintype "passive"))
      (node (ref "R22") (pin "8") (pinfunction "1_8") (pintype "passive"))
    )
    (net (code "119") (name "Net-(D11-K1)") (class "Default")
      (node (ref "D11") (pin "1") (pinfunction "K1_1") (pintype "passive"))
      (node (ref "IC6") (pin "7") (pinfunction "A4_7") (pintype "passive"))
      (node (ref "R22") (pin "5") (pinfunction "4_5") (pintype "passive"))
    )
    (net (code "120") (name "Net-(D11-K2)") (class "Default")
      (node (ref "D11") (pin "2") (pinfunction "K2_2") (pintype "passive"))
      (node (ref "IC6") (pin "5") (pinfunction "A3_5") (pintype "passive"))
      (node (ref "R22") (pin "6") (pinfunction "3_6") (pintype "passive"))
    )
    (net (code "121") (name "Net-(D12-K1)") (class "Default")
      (node (ref "D12") (pin "1") (pinfunction "K1_1") (pintype "passive"))
      (node (ref "IC5") (pin "7") (pinfunction "A4_7") (pintype "passive"))
      (node (ref "R21") (pin "5") (pinfunction "4_5") (pintype "passive"))
    )
    (net (code "122") (name "Net-(D12-K2)") (class "Default")
      (node (ref "D12") (pin "2") (pinfunction "K2_2") (pintype "passive"))
      (node (ref "IC5") (pin "5") (pinfunction "A3_5") (pintype "passive"))
      (node (ref "R21") (pin "6") (pinfunction "3_6") (pintype "passive"))
    )
    (net (code "123") (name "Net-(IC1-BOOST)") (class "Default")
      (node (ref "C2") (pin "1") (pinfunction "1_1") (pintype "passive"))
      (node (ref "IC1") (pin "6") (pinfunction "BOOST_6") (pintype "passive"))
    )
    (net (code "124") (name "Net-(IC1-SW)") (class "Default")
      (node (ref "C2") (pin "2") (pinfunction "2_2") (pintype "passive"))
      (node (ref "IC1") (pin "5") (pinfunction "SW_5") (pintype "output"))
      (node (ref "L3") (pin "2") (pinfunction "2_2") (pintype "passive"))
    )
    (net (code "125") (name "Net-(LED1-PadA)") (class "Default")
      (node (ref "LED1") (pin "A") (pinfunction "A_A") (pintype "passive"))
      (node (ref "R53") (pin "2") (pinfunction "2_2") (pintype "passive"))
    )
    (net (code "126") (name "Net-(Q1A-IN)") (class "Default")
      (node (ref "Q1") (pin "2") (pinfunction "IN_2") (pintype "input"))
      (node (ref "R15") (pin "6") (pinfunction "3_6") (pintype "passive"))
    )
    (net (code "127") (name "Net-(Q1B-IN)") (class "Default")
      (node (ref "Q1") (pin "4") (pinfunction "IN_4") (pintype "input"))
      (node (ref "R15") (pin "5") (pinfunction "4_5") (pintype "passive"))
    )
    (net (code "128") (name "Net-(Q2A-IN)") (class "Default")
      (node (ref "Q2") (pin "2") (pinfunction "IN_2") (pintype "input"))
      (node (ref "R15") (pin "8") (pinfunction "1_8") (pintype "passive"))
    )
    (net (code "129") (name "Net-(Q2B-IN)") (class "Default")
      (node (ref "Q2") (pin "4") (pinfunction "IN_4") (pintype "input"))
      (node (ref "R15") (pin "7") (pinfunction "2_7") (pintype "passive"))
    )
    (net (code "130") (name "Net-(Q3A-IN)") (class "Default")
      (node (ref "Q3") (pin "2") (pinfunction "IN_2") (pintype "input"))
      (node (ref "R1") (pin "6") (pinfunction "3_6") (pintype "passive"))
    )
    (net (code "131") (name "Net-(Q3B-IN)") (class "Default")
      (node (ref "Q3") (pin "4") (pinfunction "IN_4") (pintype "input"))
      (node (ref "R1") (pin "5") (pinfunction "4_5") (pintype "passive"))
    )
    (net (code "132") (name "Net-(Q4A-IN)") (class "Default")
      (node (ref "Q4") (pin "2") (pinfunction "IN_2") (pintype "input"))
      (node (ref "R1") (pin "8") (pinfunction "1_8") (pintype "passive"))
    )
    (net (code "133") (name "Net-(Q4B-IN)") (class "Default")
      (node (ref "Q4") (pin "4") (pinfunction "IN_4") (pintype "input"))
      (node (ref "R1") (pin "7") (pinfunction "2_7") (pintype "passive"))
    )
    (net (code "134") (name "Net-(Q5A-IN)") (class "Default")
      (node (ref "Q5") (pin "2") (pinfunction "IN_2") (pintype "input"))
      (node (ref "R2") (pin "8") (pinfunction "1_8") (pintype "passive"))
    )
    (net (code "135") (name "Net-(Q5B-IN)") (class "Default")
      (node (ref "Q5") (pin "4") (pinfunction "IN_4") (pintype "input"))
      (node (ref "R2") (pin "5") (pinfunction "4_5") (pintype "passive"))
    )
    (net (code "136") (name "Net-(Q6A-IN)") (class "Default")
      (node (ref "Q6") (pin "2") (pinfunction "IN_2") (pintype "input"))
      (node (ref "R13") (pin "6") (pinfunction "3_6") (pintype "passive"))
    )
    (net (code "137") (name "Net-(Q6B-IN)") (class "Default")
      (node (ref "Q6") (pin "4") (pinfunction "IN_4") (pintype "input"))
      (node (ref "R13") (pin "5") (pinfunction "4_5") (pintype "passive"))
    )
    (net (code "138") (name "Net-(Q7A-IN)") (class "Default")
      (node (ref "Q7") (pin "2") (pinfunction "IN_2") (pintype "input"))
      (node (ref "R13") (pin "8") (pinfunction "1_8") (pintype "passive"))
    )
    (net (code "139") (name "Net-(Q7B-IN)") (class "Default")
      (node (ref "Q7") (pin "4") (pinfunction "IN_4") (pintype "input"))
      (node (ref "R13") (pin "7") (pinfunction "2_7") (pintype "passive"))
    )
    (net (code "140") (name "Net-(Q8A-IN)") (class "Default")
      (node (ref "Q8") (pin "2") (pinfunction "IN_2") (pintype "input"))
      (node (ref "R14") (pin "6") (pinfunction "3_6") (pintype "passive"))
    )
    (net (code "141") (name "Net-(Q8B-IN)") (class "Default")
      (node (ref "Q8") (pin "4") (pinfunction "IN_4") (pintype "input"))
      (node (ref "R14") (pin "5") (pinfunction "4_5") (pintype "passive"))
    )
    (net (code "142") (name "Net-(Q9A-IN)") (class "Default")
      (node (ref "Q9") (pin "2") (pinfunction "IN_2") (pintype "input"))
      (node (ref "R14") (pin "8") (pinfunction "1_8") (pintype "passive"))
    )
    (net (code "143") (name "Net-(Q9B-IN)") (class "Default")
      (node (ref "Q9") (pin "4") (pinfunction "IN_4") (pintype "input"))
      (node (ref "R14") (pin "7") (pinfunction "2_7") (pintype "passive"))
    )
    (net (code "144") (name "unconnected-(H1-MOUNT-PadB3,2)") (class "Default")
      (node (ref "H1") (pin "B3,2") (pinfunction "MOUNT_B3,2") (pintype "passive"))
    )
    (net (code "145") (name "unconnected-(H2-MOUNT-PadB3,2)") (class "Default")
      (node (ref "H2") (pin "B3,2") (pinfunction "MOUNT_B3,2") (pintype "passive"))
    )
    (net (code "146") (name "unconnected-(H3-MOUNT-PadB3,2)") (class "Default")
      (node (ref "H3") (pin "B3,2") (pinfunction "MOUNT_B3,2") (pintype "passive"))
    )
    (net (code "147") (name "unconnected-(H4-MOUNT-PadB3,2)") (class "Default")
      (node (ref "H4") (pin "B3,2") (pinfunction "MOUNT_B3,2") (pintype "passive"))
    )
    (net (code "148") (name "unconnected-(IC8-INT-Pad1)") (class "Default")
      (node (ref "IC8") (pin "1") (pinfunction "INT_1") (pintype "bidirectional"))
    )
    (net (code "149") (name "unconnected-(IC9-INT-Pad1)") (class "Default")
      (node (ref "IC9") (pin "1") (pinfunction "INT_1") (pintype "bidirectional"))
    )
    (net (code "150") (name "unconnected-(R2-2-Pad7)") (class "Default")
      (node (ref "R2") (pin "7") (pinfunction "2_7") (pintype "passive"))
    )
    (net (code "151") (name "unconnected-(R2-3-Pad6)") (class "Default")
      (node (ref "R2") (pin "6") (pinfunction "3_6") (pintype "passive"))
    )
    (net (code "152") (name "unconnected-(R2-Pad2)") (class "Default")
      (node (ref "R2") (pin "2") (pinfunction "2_2") (pintype "passive"))
    )
    (net (code "153") (name "unconnected-(R2-Pad3)") (class "Default")
      (node (ref "R2") (pin "3") (pinfunction "3_3") (pintype "passive"))
    )
    (net (code "154") (name "unconnected-(U2-GPIO1{slash}TX0-PadTX0)") (class "Default")
      (node (ref "U2") (pin "TX0") (pinfunction "GPIO1/TX0_TX0") (pintype "output"))
    )
    (net (code "155") (name "unconnected-(U2-GPIO3{slash}RX0-PadRX0)") (class "Default")
      (node (ref "U2") (pin "RX0") (pinfunction "GPIO3/RX0_RX0") (pintype "input"))
    )
    (net (code "156") (name "unconnected-(U2-GPIO7{slash}SDO{slash}SD0{slash}~{}-PadSD0)") (class "Default")
      (node (ref "U2") (pin "SD0") (pinfunction "GPIO7/SDO/SD0/~{}_SD0") (pintype "bidirectional"))
    )
    (net (code "157") (name "unconnected-(U2-GPIO8{slash}SDI{slash}SD1{slash}~{}-PadSD1)") (class "Default")
      (node (ref "U2") (pin "SD1") (pinfunction "GPIO8/SDI/SD1/~{}_SD1") (pintype "bidirectional"))
    )
    (net (code "158") (name "unconnected-(U2-GPIO9{slash}SHD{slash}SD2{slash}~{}-PadSD2)") (class "Default")
      (node (ref "U2") (pin "SD2") (pinfunction "GPIO9/SHD/SD2/~{}_SD2") (pintype "bidirectional"))
    )
    (net (code "159") (name "unconnected-(U2-GPIO10{slash}SWP{slash}SD3{slash}~{}-PadSD3)") (class "Default")
      (node (ref "U2") (pin "SD3") (pinfunction "GPIO10/SWP/SD3/~{}_SD3") (pintype "bidirectional"))
    )
    (net (code "160") (name "unconnected-(U2-GPIO11{slash}CMD{slash}~{}-PadCMD)") (class "Default")
      (node (ref "U2") (pin "CMD") (pinfunction "GPIO11/CMD/~{}_CMD") (pintype "bidirectional"))
    )
    (net (code "161") (name "unconnected-(U2-GPIO12{slash}ADC2_5{slash}TOUCH5{slash}HSPI_Q-PadG12)") (class "Default")
      (node (ref "U2") (pin "G12") (pinfunction "GPIO12/ADC2_5/TOUCH5/HSPI_Q_G12") (pintype "bidirectional"))
    )
    (net (code "162") (name "unconnected-(U2-GPIO34{slash}ADC1_4-PadG34)") (class "Default")
      (node (ref "U2") (pin "G34") (pinfunction "GPIO34/ADC1_4_G34") (pintype "bidirectional"))
    )
    (net (code "163") (name "unconnected-(U2-GPIO35{slash}ADC1_7-PadG35)") (class "Default")
      (node (ref "U2") (pin "G35") (pinfunction "GPIO35/ADC1_7_G35") (pintype "bidirectional"))
    )
    (net (code "164") (name "unconnected-(U2-PadEN)") (class "Default")
      (node (ref "U2") (pin "EN") (pinfunction "EN_EN") (pintype "input"))
    )
    (net (code "165") (name "unconnected-(U2-VN{slash}GPIO39{slash}ADC1_3-PadSN)") (class "Default")
      (node (ref "U2") (pin "SN") (pinfunction "VN/GPIO39/ADC1_3_SN") (pintype "bidirectional"))
    )
    (net (code "166") (name "unconnected-(U2-VP{slash}GPIO36{slash}ADC1_0-PadSP)") (class "Default")
      (node (ref "U2") (pin "SP") (pinfunction "VP/GPIO36/ADC1_0_SP") (pintype "bidirectional"))
    )
  )
)
